# SCH_Tanbre_v2_latest.net
KiCad netlist of a schematic drawn in EasyEDA
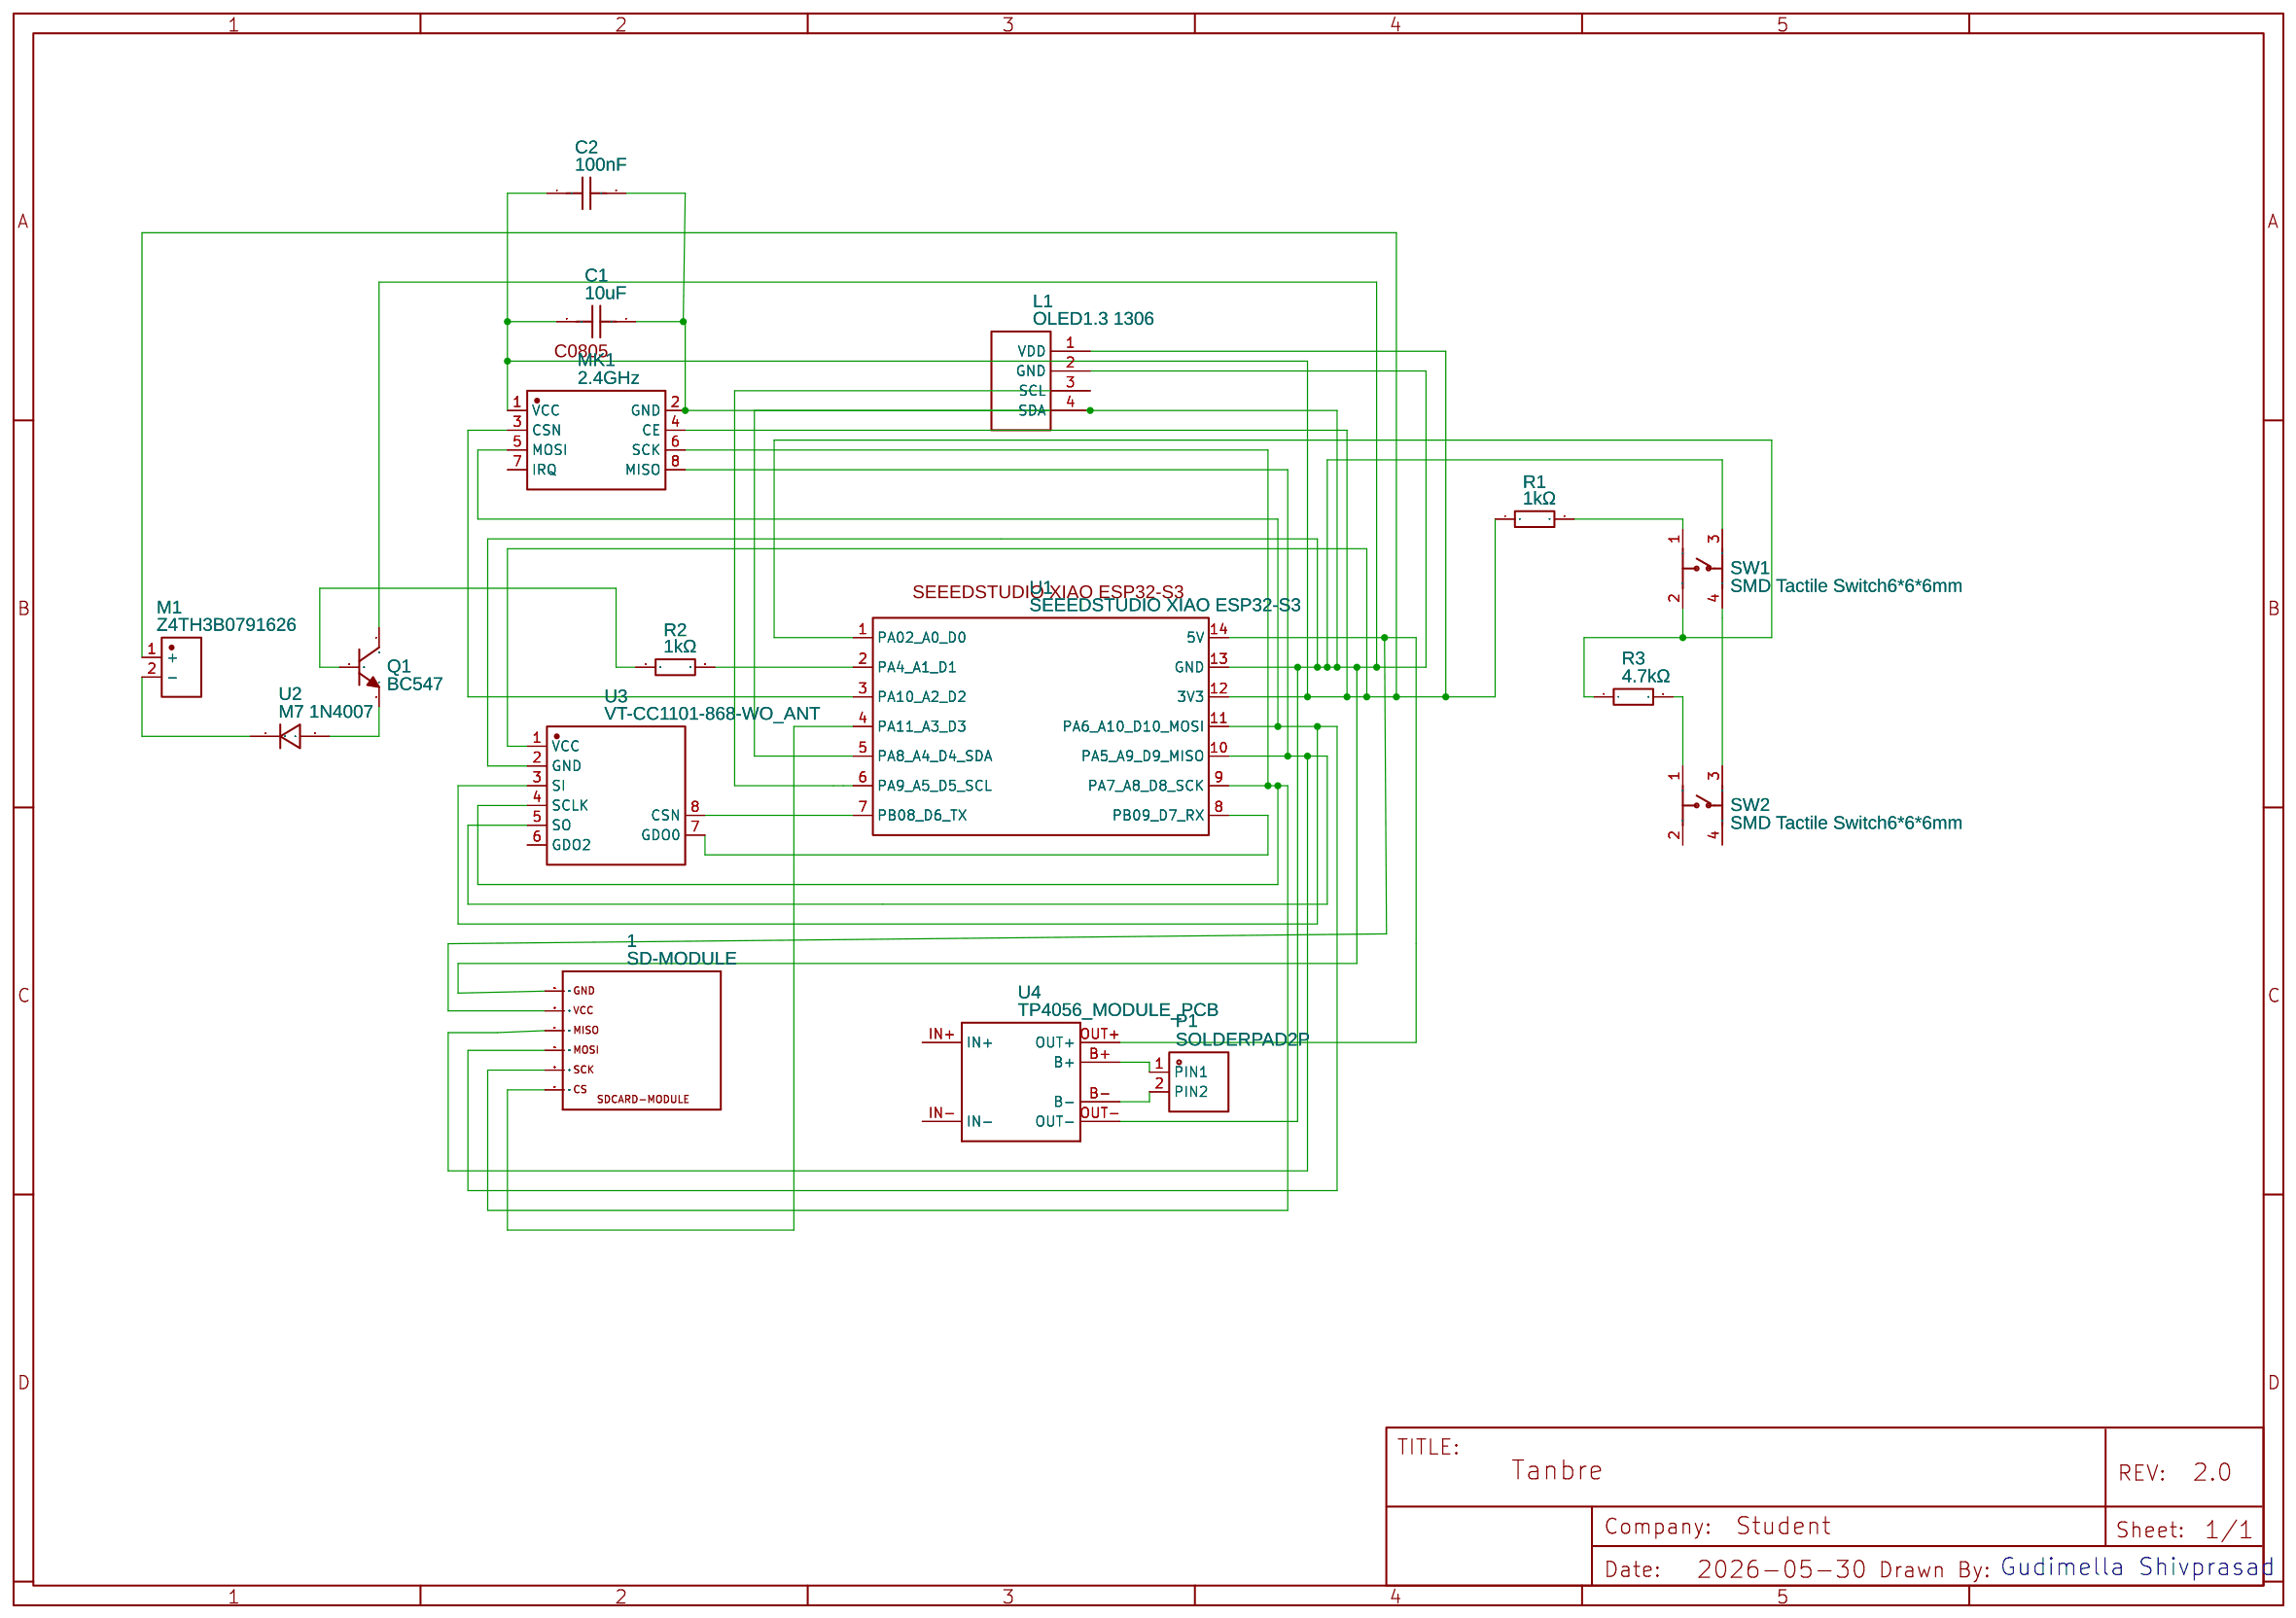
[diagram p0: schematic sheet]

(export (version "E")
  (design (tool "Eeschema 10.0.6"))
  (components
    (comp (ref "1") (value "SD-MODULE") (libsource (lib "") (part "SD-MODULE")))
    (comp (ref "C1")
      (value "10uF")
      (fields
        (field (name "Manufacturer Part") "V106K0805X5R250NHP")
        (field (name "Manufacturer") "VIIYONG(微容)")
      )
      (libsource (lib "") (part "V106K0805X5R250NHP"))
    )
    (comp (ref "C2")
      (value "100nF")
      (fields
        (field (name "Manufacturer Part") "VJ0805Y104KXXCW1BC")
        (field (name "Manufacturer") "VISHAY(威世)")
      )
      (libsource (lib "") (part "VJ0805Y104KXXCW1BC"))
    )
    (comp (ref "L1") (value "OLED1.3 1306") (libsource (lib "") (part "OLED1.3 1306")))
    (comp (ref "M1")
      (value "Z4TH3B0791626")
      (fields (field (name "Manufacturer") "KOTL(金龙机电)"))
      (libsource (lib "") (part "Z4TH3B0791626"))
    )
    (comp (ref "MK1")
      (value "2.4GHz")
      (fields (field (name "Manufacturer Part") "NF-04") (field (name "Manufacturer") "Ai-Thinker(安信可)"))
      (libsource (lib "") (part "NRF24L01"))
    )
    (comp (ref "P1")
      (value "SOLDERPAD2P")
      (fields (field (name "Manufacturer Part") "New SchematicLib"))
      (libsource (lib "") (part "SOLDERPAD2P"))
    )
    (comp (ref "Q1")
      (value "BC547")
      (fields
        (field (name "Manufacturer Part") "BC547(RANGE:420-800)")
        (field (name "Manufacturer") "CJ(江苏长电/长晶)")
      )
      (libsource (lib "") (part "BC547"))
    )
    (comp (ref "R1")
      (value "1kΩ")
      (fields (field (name "Manufacturer Part") "CR-02JL6----1K") (field (name "Manufacturer") "Viking(光颉)"))
      (libsource (lib "") (part "CR-02JL6----1K"))
    )
    (comp (ref "R2")
      (value "1kΩ")
      (fields (field (name "Manufacturer Part") "CR-02JL6----1K") (field (name "Manufacturer") "Viking(光颉)"))
      (libsource (lib "") (part "CR-02JL6----1K"))
    )
    (comp (ref "R3")
      (value "4.7kΩ")
      (fields (field (name "Manufacturer Part") "RMC12064.7K5%N") (field (name "Manufacturer") "Tyohm(幸亚电阻)"))
      (libsource (lib "") (part "RMC12064.7K5%N"))
    )
    (comp (ref "SW1")
      (value "SMD Tactile Switch6*6*6mm")
      (fields (field (name "Manufacturer Part") "贴片轻触开关6*6*6mm"))
      (libsource (lib "") (part "SMD Tactile Switch6*6*6mm"))
    )
    (comp (ref "SW2")
      (value "SMD Tactile Switch6*6*6mm")
      (fields (field (name "Manufacturer Part") "贴片轻触开关6*6*6mm"))
      (libsource (lib "") (part "SMD Tactile Switch6*6*6mm"))
    )
    (comp (ref "U1")
      (value "SEEEDSTUDIO XIAO ESP32-S3")
      (libsource (lib "") (part "SEEEDSTUDIO XIAO ESP32-S3"))
    )
    (comp (ref "U2")
      (value "M7 1N4007")
      (fields (field (name "Manufacturer") "JUXING(钜兴)"))
      (libsource (lib "") (part "M7 1N4007"))
    )
    (comp (ref "U3")
      (value "VT-CC1101-868-WO_ANT")
      (fields (field (name "Manufacturer Part") "VT-CC1101-433") (field (name "Manufacturer") "VCHIP"))
      (libsource (lib "") (part "VT-CC1101-868-WO_ANT"))
    )
    (comp (ref "U4") (value "TP4056_MODULE_PCB") (libsource (lib "") (part "TP4056_MODULE_PCB")))
  )
  (nets
    (net (code "1") (name "Net-(L1-GND)") (class "Default")
      (node (ref "1") (pin "P$6") (pinfunction "P$6_P$6") (pintype "bidirectional"))
      (node (ref "C1") (pin "2") (pinfunction "2_2") (pintype "unspecified"))
      (node (ref "C2") (pin "2") (pinfunction "2_2") (pintype "unspecified"))
      (node (ref "L1") (pin "2") (pinfunction "GND_2") (pintype "unspecified"))
      (node (ref "L1") (pin "4") (pinfunction "SDA_4") (pintype "unspecified"))
      (node (ref "MK1") (pin "2") (pinfunction "GND_2") (pintype "unspecified"))
      (node (ref "Q1") (pin "1") (pinfunction "C_1") (pintype "unspecified"))
      (node (ref "SW1") (pin "3") (pinfunction "3_3") (pintype "unspecified"))
      (node (ref "U1") (pin "13") (pinfunction "GND_13") (pintype "bidirectional"))
      (node (ref "U1") (pin "5") (pinfunction "PA8_A4_D4_SDA_5") (pintype "bidirectional"))
      (node (ref "U3") (pin "2") (pinfunction "GND_2") (pintype "unspecified"))
      (node (ref "U4") (pin "OUT-") (pinfunction "OUT-_OUT-") (pintype "passive"))
    )
    (net (code "2") (name "Net-(L1-SCL)") (class "Default")
      (node (ref "L1") (pin "3") (pinfunction "SCL_3") (pintype "unspecified"))
      (node (ref "U1") (pin "6") (pinfunction "PA9_A5_D5_SCL_6") (pintype "bidirectional"))
    )
    (net (code "3") (name "Net-(L1-VDD)") (class "Default")
      (node (ref "C1") (pin "1") (pinfunction "1_1") (pintype "unspecified"))
      (node (ref "C2") (pin "1") (pinfunction "1_1") (pintype "unspecified"))
      (node (ref "L1") (pin "1") (pinfunction "VDD_1") (pintype "unspecified"))
      (node (ref "M1") (pin "1") (pinfunction "+_1") (pintype "unspecified"))
      (node (ref "MK1") (pin "1") (pinfunction "VCC_1") (pintype "unspecified"))
      (node (ref "MK1") (pin "4") (pinfunction "CE_4") (pintype "unspecified"))
      (node (ref "R1") (pin "1") (pinfunction "1_1") (pintype "unspecified"))
      (node (ref "U1") (pin "12") (pinfunction "3V3_12") (pintype "bidirectional"))
      (node (ref "U3") (pin "1") (pinfunction "VCC_1") (pintype "unspecified"))
    )
    (net (code "4") (name "Net-(M1--)") (class "Default")
      (node (ref "M1") (pin "2") (pinfunction "-_2") (pintype "unspecified"))
      (node (ref "U2") (pin "1") (pinfunction "1_1") (pintype "unspecified"))
    )
    (net (code "5") (name "Net-(MK1-CSN)") (class "Default")
      (node (ref "MK1") (pin "3") (pinfunction "CSN_3") (pintype "unspecified"))
      (node (ref "U1") (pin "3") (pinfunction "PA10_A2_D2_3") (pintype "bidirectional"))
    )
    (net (code "6") (name "Net-(MK1-MISO)") (class "Default")
      (node (ref "1") (pin "P$4") (pinfunction "P$4_P$4") (pintype "bidirectional"))
      (node (ref "MK1") (pin "8") (pinfunction "MISO_8") (pintype "unspecified"))
      (node (ref "U1") (pin "10") (pinfunction "PA5_A9_D9_MISO_10") (pintype "bidirectional"))
      (node (ref "U3") (pin "5") (pinfunction "SO_5") (pintype "unspecified"))
    )
    (net (code "7") (name "Net-(MK1-MOSI)") (class "Default")
      (node (ref "1") (pin "P$3") (pinfunction "P$3_P$3") (pintype "bidirectional"))
      (node (ref "MK1") (pin "5") (pinfunction "MOSI_5") (pintype "unspecified"))
      (node (ref "U1") (pin "11") (pinfunction "PA6_A10_D10_MOSI_11") (pintype "bidirectional"))
      (node (ref "U3") (pin "3") (pinfunction "SI_3") (pintype "unspecified"))
    )
    (net (code "8") (name "Net-(MK1-SCK)") (class "Default")
      (node (ref "1") (pin "P$2") (pinfunction "P$2_P$2") (pintype "bidirectional"))
      (node (ref "MK1") (pin "6") (pinfunction "SCK_6") (pintype "unspecified"))
      (node (ref "U1") (pin "9") (pinfunction "PA7_A8_D8_SCK_9") (pintype "bidirectional"))
      (node (ref "U3") (pin "4") (pinfunction "SCLK_4") (pintype "unspecified"))
    )
    (net (code "9") (name "Net-(P1-PIN1)") (class "Default")
      (node (ref "P1") (pin "1") (pinfunction "PIN1_1") (pintype "unspecified"))
      (node (ref "U4") (pin "B+") (pinfunction "B+_B+") (pintype "passive"))
    )
    (net (code "10") (name "Net-(P1-PIN2)") (class "Default")
      (node (ref "P1") (pin "2") (pinfunction "PIN2_2") (pintype "unspecified"))
      (node (ref "U4") (pin "B-") (pinfunction "B-_B-") (pintype "passive"))
    )
    (net (code "11") (name "Net-(Q1-B)") (class "Default")
      (node (ref "Q1") (pin "2") (pinfunction "B_2") (pintype "unspecified"))
      (node (ref "R2") (pin "1") (pinfunction "1_1") (pintype "unspecified"))
    )
    (net (code "12") (name "Net-(Q1-E)") (class "Default")
      (node (ref "Q1") (pin "3") (pinfunction "E_3") (pintype "unspecified"))
      (node (ref "U2") (pin "2") (pinfunction "2_2") (pintype "unspecified"))
    )
    (net (code "13") (name "Net-(R1-Pad2)") (class "Default")
      (node (ref "R1") (pin "2") (pinfunction "2_2") (pintype "unspecified"))
      (node (ref "SW1") (pin "1") (pinfunction "1_1") (pintype "unspecified"))
    )
    (net (code "14") (name "Net-(R3-Pad2)") (class "Default")
      (node (ref "R3") (pin "2") (pinfunction "2_2") (pintype "unspecified"))
      (node (ref "SW2") (pin "1") (pinfunction "1_1") (pintype "unspecified"))
    )
    (net (code "15") (name "Net-(SW1-Pad4)") (class "Default")
      (node (ref "SW1") (pin "4") (pinfunction "4_4") (pintype "unspecified"))
      (node (ref "SW2") (pin "3") (pinfunction "3_3") (pintype "unspecified"))
    )
    (net (code "16") (name "Net-(U1-5V)") (class "Default")
      (node (ref "1") (pin "P$5") (pinfunction "P$5_P$5") (pintype "bidirectional"))
      (node (ref "U1") (pin "14") (pinfunction "5V_14") (pintype "bidirectional"))
      (node (ref "U4") (pin "OUT+") (pinfunction "OUT+_OUT+") (pintype "passive"))
    )
    (net (code "17") (name "Net-(U1-PA02_A0_D0)") (class "Default")
      (node (ref "R3") (pin "1") (pinfunction "1_1") (pintype "unspecified"))
      (node (ref "SW1") (pin "2") (pinfunction "2_2") (pintype "unspecified"))
      (node (ref "U1") (pin "1") (pinfunction "PA02_A0_D0_1") (pintype "bidirectional"))
    )
    (net (code "18") (name "Net-(U1-PA4_A1_D1)") (class "Default")
      (node (ref "R2") (pin "2") (pinfunction "2_2") (pintype "unspecified"))
      (node (ref "U1") (pin "2") (pinfunction "PA4_A1_D1_2") (pintype "bidirectional"))
    )
    (net (code "19") (name "Net-(U1-PA11_A3_D3)") (class "Default")
      (node (ref "1") (pin "P$1") (pinfunction "P$1_P$1") (pintype "bidirectional"))
      (node (ref "U1") (pin "4") (pinfunction "PA11_A3_D3_4") (pintype "bidirectional"))
    )
    (net (code "20") (name "Net-(U1-PB08_D6_TX)") (class "Default")
      (node (ref "U1") (pin "7") (pinfunction "PB08_D6_TX_7") (pintype "bidirectional"))
      (node (ref "U3") (pin "8") (pinfunction "CSN_8") (pintype "unspecified"))
    )
    (net (code "21") (name "Net-(U1-PB09_D7_RX)") (class "Default")
      (node (ref "U1") (pin "8") (pinfunction "PB09_D7_RX_8") (pintype "bidirectional"))
      (node (ref "U3") (pin "7") (pinfunction "GDO0_7") (pintype "unspecified"))
    )
    (net (code "22") (name "unconnected-(MK1-IRQ-Pad7)") (class "Default")
      (node (ref "MK1") (pin "7") (pinfunction "IRQ_7") (pintype "unspecified"))
    )
    (net (code "23") (name "unconnected-(SW2-Pad2)") (class "Default")
      (node (ref "SW2") (pin "2") (pinfunction "2_2") (pintype "unspecified"))
    )
    (net (code "24") (name "unconnected-(SW2-Pad4)") (class "Default")
      (node (ref "SW2") (pin "4") (pinfunction "4_4") (pintype "unspecified"))
    )
    (net (code "25") (name "unconnected-(U3-GDO2-Pad6)") (class "Default")
      (node (ref "U3") (pin "6") (pinfunction "GDO2_6") (pintype "unspecified"))
    )
    (net (code "26") (name "unconnected-(U4-PadIN+)") (class "Default")
      (node (ref "U4") (pin "IN+") (pinfunction "IN+_IN+") (pintype "passive"))
    )
    (net (code "27") (name "unconnected-(U4-PadIN-)") (class "Default")
      (node (ref "U4") (pin "IN-") (pinfunction "IN-_IN-") (pintype "passive"))
    )
  )
)
